# door-strike-schematic.net
KiCad netlist of a schematic drawn in EAGLE
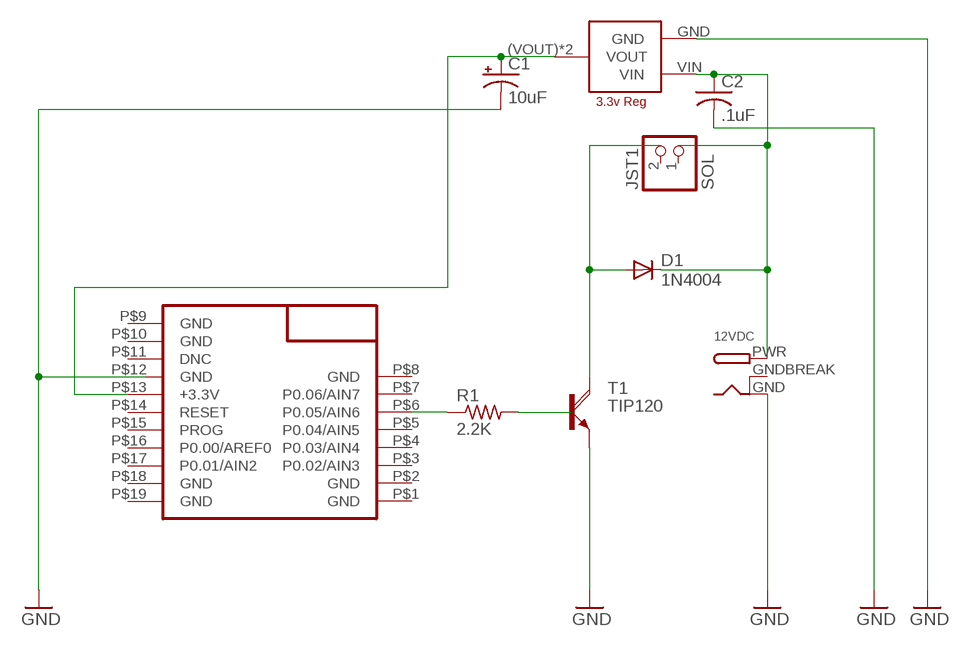
[diagram p0: schematic, sheet 1]

(export (version "E")
  (design (tool "Eeschema 10.0.6"))
  (components
    (comp (ref "12VDC")
      (value "DCBARRELPTH")
      (footprint "eagle-import:DCJACK_2MM_PTH")
      (libsource (lib "eagle-import") (part "DCBARRELPTH"))
    )
    (comp (ref "C1")
      (value "10uF")
      (footprint "eagle-import:E2-5")
      (libsource (lib "eagle-import") (part "CPOL-USE2-5"))
    )
    (comp (ref "C2")
      (value ".1uF")
      (footprint "eagle-import:C102-054X133")
      (libsource (lib "eagle-import") (part "C-US102-054X133"))
    )
    (comp (ref "D1")
      (value "1N4004")
      (footprint "eagle-import:DO41-10")
      (libsource (lib "eagle-import") (part "1N4004"))
    )
    (comp (ref "JST1")
      (value "SOL")
      (footprint "eagle-import:JST-PH-2-THM")
      (libsource (lib "eagle-import") (part "JST_2PIN-THM"))
    )
    (comp (ref "R1")
      (value "2.2K")
      (footprint "eagle-import:0207_7")
      (libsource (lib "eagle-import") (part "R-US_0207/7"))
    )
    (comp (ref "T1")
      (value "TIP120")
      (footprint "eagle-import:TO220AH")
      (libsource (lib "eagle-import") (part "TIP120"))
    )
    (comp (ref "U$1")
      (value "LD1117")
      (footprint "eagle-import:LD1117SOT-223")
      (libsource (lib "eagle-import") (part "LD1117"))
    )
    (comp (ref "U$2")
      (value "RFD22301")
      (footprint "eagle-import:RFD21733")
      (libsource (lib "eagle-import") (part "RFD22301"))
    )
  )
  (nets
    (net (code "1") (name "/GNDBREAK") (class "Default")
      (node (ref "12VDC") (pin "GNDBREAK") (pinfunction "GNDBREAK_GNDBREAK") (pintype "power_in"))
    )
    (net (code "2") (name "GND") (class "Default")
      (node (ref "12VDC") (pin "GND") (pinfunction "GND_GND") (pintype "power_in"))
      (node (ref "C1") (pin "-") (pinfunction "-_-") (pintype "passive"))
      (node (ref "C2") (pin "2") (pinfunction "2_2") (pintype "passive"))
      (node (ref "T1") (pin "E") (pinfunction "E_E") (pintype "passive"))
      (node (ref "U$1") (pin "GND") (pinfunction "GND_GND") (pintype "bidirectional"))
    )
    (net (code "3") (name "Net-(12VDC-PadPWR)") (class "Default")
      (node (ref "12VDC") (pin "PWR") (pinfunction "PWR_PWR") (pintype "power_in"))
      (node (ref "C2") (pin "1") (pinfunction "1_1") (pintype "passive"))
      (node (ref "D1") (pin "C") (pinfunction "C_C") (pintype "passive"))
      (node (ref "U$1") (pin "VIN") (pinfunction "VIN_VIN") (pintype "bidirectional"))
    )
    (net (code "4") (name "Net-(D1-PadA)") (class "Default")
      (node (ref "D1") (pin "A") (pinfunction "A_A") (pintype "passive"))
      (node (ref "T1") (pin "C") (pinfunction "C_C") (pintype "passive"))
    )
    (net (code "5") (name "Net-(U$2-+3.3V)") (class "Default")
      (node (ref "C1") (pin "+") (pinfunction "+_+") (pintype "passive"))
      (node (ref "U$1") (pin "(VOUT)") (pinfunction "VOUT_(VOUT)") (pintype "bidirectional"))
      (node (ref "U$1") (pin "VOUT") (pinfunction "VOUT_VOUT") (pintype "bidirectional"))
      (node (ref "U$2") (pin "P$13") (pinfunction "+3.3V_P$13") (pintype "bidirectional"))
    )
    (net (code "6") (name "Net-(U$2-P0.05{slash}AIN6)") (class "Default")
      (node (ref "R1") (pin "1") (pinfunction "1_1") (pintype "passive"))
      (node (ref "U$2") (pin "P$6") (pinfunction "P0.05/AIN6_P$6") (pintype "bidirectional"))
    )
    (net (code "7") (name "unconnected-(JST1-1-Pad2)") (class "Default")
      (node (ref "JST1") (pin "2") (pinfunction "1_2") (pintype "passive"))
    )
    (net (code "8") (name "unconnected-(JST1-2-Pad1)") (class "Default")
      (node (ref "JST1") (pin "1") (pinfunction "2_1") (pintype "passive"))
    )
    (net (code "9") (name "unconnected-(R1-Pad2)") (class "Default")
      (node (ref "R1") (pin "2") (pinfunction "2_2") (pintype "passive"))
    )
    (net (code "10") (name "unconnected-(T1-PadB)") (class "Default")
      (node (ref "T1") (pin "B") (pinfunction "B_B") (pintype "passive"))
    )
    (net (code "11") (name "unconnected-(U$2-DNC-PadP$11)") (class "Default")
      (node (ref "U$2") (pin "P$11") (pinfunction "DNC_P$11") (pintype "bidirectional"))
    )
    (net (code "12") (name "unconnected-(U$2-GND-PadP$1)") (class "Default")
      (node (ref "U$2") (pin "P$1") (pinfunction "GND_P$1") (pintype "bidirectional"))
    )
    (net (code "13") (name "unconnected-(U$2-GND-PadP$2)") (class "Default")
      (node (ref "U$2") (pin "P$2") (pinfunction "GND_P$2") (pintype "bidirectional"))
    )
    (net (code "14") (name "unconnected-(U$2-GND-PadP$8)") (class "Default")
      (node (ref "U$2") (pin "P$8") (pinfunction "GND_P$8") (pintype "bidirectional"))
    )
    (net (code "15") (name "unconnected-(U$2-GND-PadP$9)") (class "Default")
      (node (ref "U$2") (pin "P$9") (pinfunction "GND_P$9") (pintype "bidirectional"))
    )
    (net (code "16") (name "unconnected-(U$2-GND-PadP$10)") (class "Default")
      (node (ref "U$2") (pin "P$10") (pinfunction "GND_P$10") (pintype "bidirectional"))
    )
    (net (code "17") (name "unconnected-(U$2-GND-PadP$12)") (class "Default")
      (node (ref "U$2") (pin "P$12") (pinfunction "GND_P$12") (pintype "bidirectional"))
    )
    (net (code "18") (name "unconnected-(U$2-GND-PadP$18)") (class "Default")
      (node (ref "U$2") (pin "P$18") (pinfunction "GND_P$18") (pintype "bidirectional"))
    )
    (net (code "19") (name "unconnected-(U$2-GND-PadP$19)") (class "Default")
      (node (ref "U$2") (pin "P$19") (pinfunction "GND_P$19") (pintype "bidirectional"))
    )
    (net (code "20") (name "unconnected-(U$2-P0.00{slash}AREF0-PadP$16)") (class "Default")
      (node (ref "U$2") (pin "P$16") (pinfunction "P0.00/AREF0_P$16") (pintype "bidirectional"))
    )
    (net (code "21") (name "unconnected-(U$2-P0.01{slash}AIN2-PadP$17)") (class "Default")
      (node (ref "U$2") (pin "P$17") (pinfunction "P0.01/AIN2_P$17") (pintype "bidirectional"))
    )
    (net (code "22") (name "unconnected-(U$2-P0.02{slash}AIN3-PadP$3)") (class "Default")
      (node (ref "U$2") (pin "P$3") (pinfunction "P0.02/AIN3_P$3") (pintype "bidirectional"))
    )
    (net (code "23") (name "unconnected-(U$2-P0.03{slash}AIN4-PadP$4)") (class "Default")
      (node (ref "U$2") (pin "P$4") (pinfunction "P0.03/AIN4_P$4") (pintype "bidirectional"))
    )
    (net (code "24") (name "unconnected-(U$2-P0.04{slash}AIN5-PadP$5)") (class "Default")
      (node (ref "U$2") (pin "P$5") (pinfunction "P0.04/AIN5_P$5") (pintype "bidirectional"))
    )
    (net (code "25") (name "unconnected-(U$2-P0.06{slash}AIN7-PadP$7)") (class "Default")
      (node (ref "U$2") (pin "P$7") (pinfunction "P0.06/AIN7_P$7") (pintype "bidirectional"))
    )
    (net (code "26") (name "unconnected-(U$2-PROG-PadP$15)") (class "Default")
      (node (ref "U$2") (pin "P$15") (pinfunction "PROG_P$15") (pintype "bidirectional"))
    )
    (net (code "27") (name "unconnected-(U$2-RESET-PadP$14)") (class "Default")
      (node (ref "U$2") (pin "P$14") (pinfunction "RESET_P$14") (pintype "bidirectional"))
    )
  )
)
